# CHARGER.net
KiCad netlist of a schematic drawn in Altium Designer
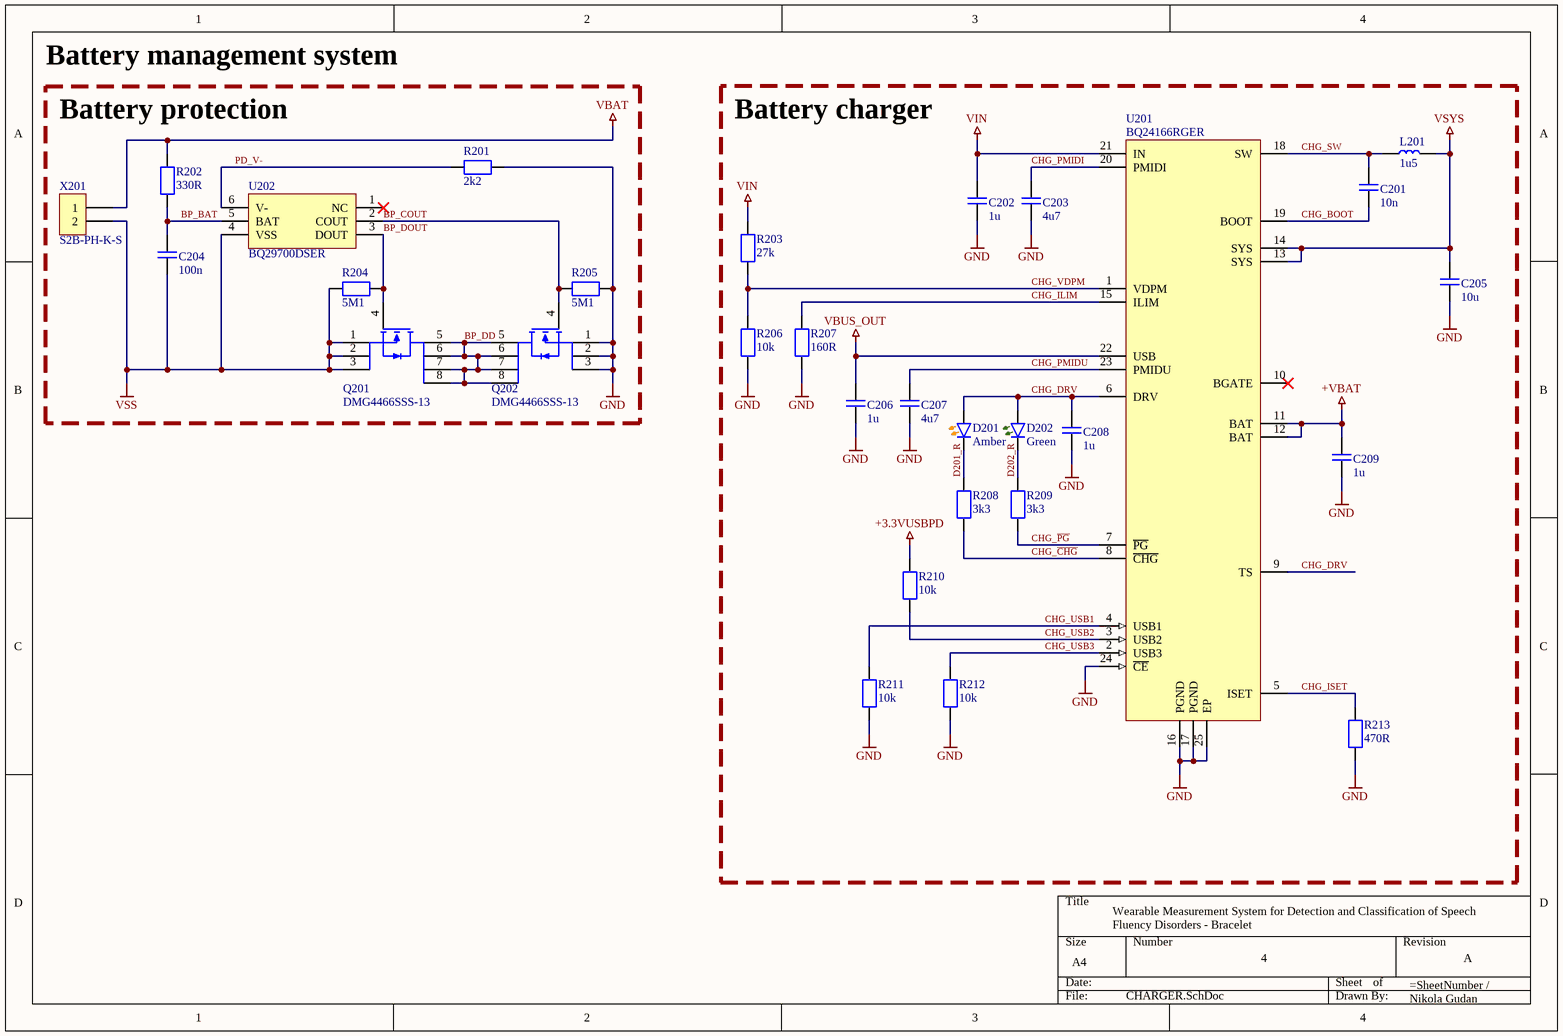
[diagram p0: CHARGER.SchDoc]

(export (version "E")
  (design (tool "Eeschema 10.0.6"))
  (components
    (comp (ref "C201")
      (value "10n")
      (footprint "CAPC0603")
      (description "Ceramic capacitor, 10nF,  50V, X7R")
      (fields (field (name "MFR") "KEMET") (field (name "CHECKED") "Yes"))
      (libsource (lib "NG_Passive") (part "CAPC0603-10n-20"))
    )
    (comp (ref "C202")
      (value "1u")
      (footprint "CAPC0603")
      (description "Ceramic capacitor, 1uF,  50V, X5R")
      (fields (field (name "MFR") "Murata Electronics") (field (name "CHECKED") "Yes"))
      (libsource (lib "NG_Passive") (part "CAPC0603-1u-10"))
    )
    (comp (ref "C203")
      (value "4u7")
      (footprint "CAPC0603")
      (description "Ceramic capacitor, 4.7uF, 25V, X5R")
      (fields (field (name "MFR") "TDK") (field (name "CHECKED") "Yes"))
      (libsource (lib "NG_Passive") (part "CAPC0603-4u7-10"))
    )
    (comp (ref "C204")
      (value "100n")
      (footprint "CAPC0603")
      (description "Ceramic capacitor, 100nF,  50V, X7R")
      (fields (field (name "MFR") "KEMET") (field (name "CHECKED") "Yes"))
      (libsource (lib "NG_Passive") (part "CAPC0603-100n-10"))
    )
    (comp (ref "C205")
      (value "10u")
      (footprint "CAPC0603")
      (description "Ceramic capacitor, 10uF,  25V, X5R")
      (fields (field (name "MFR") "TAIYO YUDEN") (field (name "CHECKED") "Yes"))
      (libsource (lib "NG_Passive") (part "CAPC0603-10u-20"))
    )
    (comp (ref "C206")
      (value "1u")
      (footprint "CAPC0603")
      (description "Ceramic capacitor, 1uF,  50V, X5R")
      (fields (field (name "MFR") "Murata Electronics") (field (name "CHECKED") "Yes"))
      (libsource (lib "NG_Passive") (part "CAPC0603-1u-10"))
    )
    (comp (ref "C207")
      (value "4u7")
      (footprint "CAPC0603")
      (description "Ceramic capacitor, 4.7uF, 25V, X5R")
      (fields (field (name "MFR") "TDK") (field (name "CHECKED") "Yes"))
      (libsource (lib "NG_Passive") (part "CAPC0603-4u7-10"))
    )
    (comp (ref "C208")
      (value "1u")
      (footprint "CAPC0603")
      (description "Ceramic capacitor, 1uF,  50V, X5R")
      (fields (field (name "MFR") "Murata Electronics") (field (name "CHECKED") "Yes"))
      (libsource (lib "NG_Passive") (part "CAPC0603-1u-10"))
    )
    (comp (ref "C209")
      (value "1u")
      (footprint "CAPC0603")
      (description "Ceramic capacitor, 1uF,  50V, X5R")
      (fields (field (name "MFR") "Murata Electronics") (field (name "CHECKED") "Yes"))
      (libsource (lib "NG_Passive") (part "CAPC0603-1u-10"))
    )
    (comp (ref "D201")
      (value "Amber")
      (footprint "LED0603")
      (description "LED Amber, 2V, 30mA")
      (fields (field (name "MFR") "Würth Elektronik") (field (name "CHECKED") "Yes"))
      (libsource (lib "NG_Active") (part "150060AS75000"))
    )
    (comp (ref "D202")
      (value "Green")
      (footprint "LED0603")
      (description "LED Green, 2.1V, 20mA")
      (fields (field (name "MFR") "Wurth Elektronik") (field (name "CHECKED") "Yes"))
      (libsource (lib "NG_Active") (part "150060GS75000"))
    )
    (comp (ref "L201")
      (value "1u5")
      (footprint "INDC1008")
      (description "Inductor 1.5uH, 3.3A, ±20%, 60mOhm")
      (fields (field (name "MFR") "TDK") (field (name "CHECKED") "Yes"))
      (libsource (lib "NG_Passive") (part "INDC1008-1u5-20"))
    )
    (comp (ref "Q201")
      (value "DMG4466SSS-13")
      (footprint "SOIC127P610X175-8")
      (description "MOSFET, N-CH, 30V, 10A")
      (fields (field (name "MFR") "Diodes Incorporated") (field (name "CHECKED") "Yes"))
      (libsource (lib "NG_Active") (part "DMG4466SSS-13"))
    )
    (comp (ref "Q202")
      (value "DMG4466SSS-13")
      (footprint "SOIC127P610X175-8")
      (description "MOSFET, N-CH, 30V, 10A")
      (fields (field (name "MFR") "Diodes Incorporated") (field (name "CHECKED") "Yes"))
      (libsource (lib "NG_Active") (part "DMG4466SSS-13"))
    )
    (comp (ref "R201")
      (value "2k2")
      (footprint "RESC0603")
      (description "Thick film resistor, 2.2kOhms, 100mW")
      (fields (field (name "MFR") "YAGEO") (field (name "CHECKED") "Yes"))
      (libsource (lib "NG_Passive") (part "RES0603-2k2-1"))
    )
    (comp (ref "R202")
      (value "330R")
      (footprint "RESC0603")
      (description "Thick film resistor, 330Ohms, 100mW")
      (fields (field (name "MFR") "YAGEO") (field (name "CHECKED") "Yes"))
      (libsource (lib "NG_Passive") (part "RES0603-330R-1"))
    )
    (comp (ref "R203")
      (value "27k")
      (footprint "RESC0603")
      (description "Thick film resistor, 27kOhm, 100mW")
      (fields (field (name "MFR") "YAGEO") (field (name "CHECKED") "Yes"))
      (libsource (lib "NG_Passive") (part "RES0603-27-1"))
    )
    (comp (ref "R204")
      (value "5M1")
      (footprint "RESC0603")
      (description "Thick film resistor, 5.1MOhms, 100mW")
      (fields (field (name "MFR") "YAGEO") (field (name "CHECKED") "Yes"))
      (libsource (lib "NG_Passive") (part "RES0603-5M1-1"))
    )
    (comp (ref "R205")
      (value "5M1")
      (footprint "RESC0603")
      (description "Thick film resistor, 5.1MOhms, 100mW")
      (fields (field (name "MFR") "YAGEO") (field (name "CHECKED") "Yes"))
      (libsource (lib "NG_Passive") (part "RES0603-5M1-1"))
    )
    (comp (ref "R206")
      (value "10k")
      (footprint "RESC0603")
      (description "Thick film resistor, 10kOhm, 100mW")
      (fields (field (name "MFR") "YAGEO") (field (name "CHECKED") "Yes"))
      (libsource (lib "NG_Passive") (part "RES0603-10k-1"))
    )
    (comp (ref "R207")
      (value "160R")
      (footprint "RESC0603")
      (description "Thick film resistor, 160Ohms, 100mW")
      (fields (field (name "MFR") "Panasonic") (field (name "CHECKED") "Yes"))
      (libsource (lib "NG_Passive") (part "RES0603-160R-1"))
    )
    (comp (ref "R208")
      (value "3k3")
      (footprint "RESC0603")
      (description "Thick film resistor, 3.3kOhms, 100mW")
      (fields (field (name "MFR") "YAGEO") (field (name "CHECKED") "Yes"))
      (libsource (lib "NG_Passive") (part "RES0603-3k3-1"))
    )
    (comp (ref "R209")
      (value "3k3")
      (footprint "RESC0603")
      (description "Thick film resistor, 3.3kOhms, 100mW")
      (fields (field (name "MFR") "YAGEO") (field (name "CHECKED") "Yes"))
      (libsource (lib "NG_Passive") (part "RES0603-3k3-1"))
    )
    (comp (ref "R210")
      (value "10k")
      (footprint "RESC0603")
      (description "Thick film resistor, 10kOhm, 100mW")
      (fields (field (name "MFR") "YAGEO") (field (name "CHECKED") "Yes"))
      (libsource (lib "NG_Passive") (part "RES0603-10k-1"))
    )
    (comp (ref "R211")
      (value "10k")
      (footprint "RESC0603")
      (description "Thick film resistor, 10kOhm, 100mW")
      (fields (field (name "MFR") "YAGEO") (field (name "CHECKED") "Yes"))
      (libsource (lib "NG_Passive") (part "RES0603-10k-1"))
    )
    (comp (ref "R212")
      (value "10k")
      (footprint "RESC0603")
      (description "Thick film resistor, 10kOhm, 100mW")
      (fields (field (name "MFR") "YAGEO") (field (name "CHECKED") "Yes"))
      (libsource (lib "NG_Passive") (part "RES0603-10k-1"))
    )
    (comp (ref "R213")
      (value "470R")
      (footprint "RESC0603")
      (description "Thick film resistor, 470R, 100mW")
      (fields (field (name "MFR") "YAGEO") (field (name "CHECKED") "Yes"))
      (libsource (lib "NG_Passive") (part "RES0603-470R-1"))
    )
    (comp (ref "U201")
      (value "BQ24166RGER")
      (footprint "QFN50P410X410X100-24EP")
      (description "IC Battery Charger, Li-Ion, 1 Cell, 3.7V, 2.5A")
      (fields (field (name "MFR") "Texas Instruments") (field (name "CHECKED") "Yes"))
      (libsource (lib "NG_Analog") (part "IC BATT CHG LI-ION BQ24166"))
    )
    (comp (ref "U202")
      (value "BQ29700DSER")
      (footprint "WSON50P150X150X80-6")
      (description "Battery Protection IC Li-Ion 1Cell")
      (fields (field (name "MFR") "Texas Instruments") (field (name "CHECKED") "Yes"))
      (libsource (lib "NG_Analog") (part "IC BATT PROT BQ29700DSER"))
    )
    (comp (ref "X201")
      (value "S2B-PH-K-S")
      (footprint "JST_S2B-PH-K-S")
      (description "JST PH Connector 2POS R/A THT")
      (fields (field (name "MFR") "JST Sales America Inc.") (field (name "CHECKED") "Yes"))
      (libsource (lib "NG_Mechanical") (part "JST S2B-PH-K-S"))
    )
  )
  (nets
    (net (code "1") (name "+3.3VUSBPD") (class "Default")
      (node (ref "R210") (pin "1") (pinfunction "1_1") (pintype "passive"))
    )
    (net (code "2") (name "+VBAT") (class "Default")
      (node (ref "C209") (pin "2") (pinfunction "2_2") (pintype "passive"))
      (node (ref "U201") (pin "11") (pinfunction "BAT_11") (pintype "power_in"))
      (node (ref "U201") (pin "12") (pinfunction "BAT_12") (pintype "power_in"))
    )
    (net (code "3") (name "/BP_BAT") (class "Default")
      (node (ref "C204") (pin "2") (pinfunction "2_2") (pintype "passive"))
      (node (ref "R202") (pin "1") (pinfunction "1_1") (pintype "passive"))
      (node (ref "U202") (pin "5") (pinfunction "BAT_5") (pintype "power_in"))
    )
    (net (code "4") (name "/BP_COUT") (class "Default")
      (node (ref "Q202") (pin "4") (pinfunction "G_4") (pintype "passive"))
      (node (ref "R205") (pin "2") (pinfunction "2_2") (pintype "passive"))
      (node (ref "U202") (pin "2") (pinfunction "COUT_2") (pintype "passive"))
    )
    (net (code "5") (name "/BP_DD") (class "Default")
      (node (ref "Q201") (pin "5") (pinfunction "D_5") (pintype "passive"))
      (node (ref "Q201") (pin "6") (pinfunction "D_6") (pintype "passive"))
      (node (ref "Q201") (pin "7") (pinfunction "D_7") (pintype "passive"))
      (node (ref "Q201") (pin "8") (pinfunction "D_8") (pintype "passive"))
      (node (ref "Q202") (pin "5") (pinfunction "D_5") (pintype "passive"))
      (node (ref "Q202") (pin "6") (pinfunction "D_6") (pintype "passive"))
      (node (ref "Q202") (pin "7") (pinfunction "D_7") (pintype "passive"))
      (node (ref "Q202") (pin "8") (pinfunction "D_8") (pintype "passive"))
    )
    (net (code "6") (name "/BP_DOUT") (class "Default")
      (node (ref "Q201") (pin "4") (pinfunction "G_4") (pintype "passive"))
      (node (ref "R204") (pin "1") (pinfunction "1_1") (pintype "passive"))
      (node (ref "U202") (pin "3") (pinfunction "DOUT_3") (pintype "passive"))
    )
    (net (code "7") (name "/CHG_BOOT") (class "Default")
      (node (ref "C201") (pin "1") (pinfunction "1_1") (pintype "passive"))
      (node (ref "U201") (pin "19") (pinfunction "BOOT_19") (pintype "passive"))
    )
    (net (code "8") (name "/CHG_DRV") (class "Default")
      (node (ref "C208") (pin "2") (pinfunction "2_2") (pintype "passive"))
      (node (ref "D201") (pin "2") (pinfunction "2_2") (pintype "passive"))
      (node (ref "D202") (pin "2") (pinfunction "2_2") (pintype "passive"))
      (node (ref "U201") (pin "6") (pinfunction "DRV_6") (pintype "passive"))
      (node (ref "U201") (pin "9") (pinfunction "TS_9") (pintype "passive"))
    )
    (net (code "9") (name "/CHG_ILIM") (class "Default")
      (node (ref "R207") (pin "1") (pinfunction "1_1") (pintype "passive"))
      (node (ref "U201") (pin "15") (pinfunction "ILIM_15") (pintype "power_in"))
    )
    (net (code "10") (name "/CHG_ISET") (class "Default")
      (node (ref "R213") (pin "2") (pinfunction "2_2") (pintype "passive"))
      (node (ref "U201") (pin "5") (pinfunction "ISET_5") (pintype "passive"))
    )
    (net (code "11") (name "/CHG_PMIDI") (class "Default")
      (node (ref "C203") (pin "2") (pinfunction "2_2") (pintype "passive"))
      (node (ref "U201") (pin "20") (pinfunction "PMIDI_20") (pintype "power_in"))
    )
    (net (code "12") (name "/CHG_PMIDU") (class "Default")
      (node (ref "C207") (pin "2") (pinfunction "2_2") (pintype "passive"))
      (node (ref "U201") (pin "23") (pinfunction "PMIDU_23") (pintype "power_in"))
    )
    (net (code "13") (name "/CHG_SW") (class "Default")
      (node (ref "C201") (pin "2") (pinfunction "2_2") (pintype "passive"))
      (node (ref "L201") (pin "1") (pinfunction "1_1") (pintype "passive"))
      (node (ref "U201") (pin "18") (pinfunction "SW_18") (pintype "power_in"))
    )
    (net (code "14") (name "/CHG_USB1") (class "Default")
      (node (ref "R211") (pin "1") (pinfunction "1_1") (pintype "passive"))
      (node (ref "U201") (pin "4") (pinfunction "USB1_4") (pintype "input"))
    )
    (net (code "15") (name "/CHG_USB2") (class "Default")
      (node (ref "R210") (pin "2") (pinfunction "2_2") (pintype "passive"))
      (node (ref "U201") (pin "3") (pinfunction "USB2_3") (pintype "input"))
    )
    (net (code "16") (name "/CHG_USB3") (class "Default")
      (node (ref "R212") (pin "1") (pinfunction "1_1") (pintype "passive"))
      (node (ref "U201") (pin "2") (pinfunction "USB3_2") (pintype "input"))
    )
    (net (code "17") (name "/CHG_VDPM") (class "Default")
      (node (ref "R203") (pin "1") (pinfunction "1_1") (pintype "passive"))
      (node (ref "R206") (pin "2") (pinfunction "2_2") (pintype "passive"))
      (node (ref "U201") (pin "1") (pinfunction "VDPM_1") (pintype "power_in"))
    )
    (net (code "18") (name "/CHG_~{CHG}") (class "Default")
      (node (ref "R208") (pin "1") (pinfunction "1_1") (pintype "passive"))
      (node (ref "U201") (pin "8") (pinfunction "~{CHG}_8") (pintype "open_collector"))
    )
    (net (code "19") (name "/CHG_~{PG}") (class "Default")
      (node (ref "R209") (pin "1") (pinfunction "1_1") (pintype "passive"))
      (node (ref "U201") (pin "7") (pinfunction "~{PG}_7") (pintype "open_collector"))
    )
    (net (code "20") (name "/D201_R") (class "Default")
      (node (ref "D201") (pin "1") (pinfunction "1_1") (pintype "passive"))
      (node (ref "R208") (pin "2") (pinfunction "2_2") (pintype "passive"))
    )
    (net (code "21") (name "/D202_R") (class "Default")
      (node (ref "D202") (pin "1") (pinfunction "1_1") (pintype "passive"))
      (node (ref "R209") (pin "2") (pinfunction "2_2") (pintype "passive"))
    )
    (net (code "22") (name "/PD_V-") (class "Default")
      (node (ref "R201") (pin "2") (pinfunction "2_2") (pintype "passive"))
      (node (ref "U202") (pin "6") (pinfunction "V-_6") (pintype "power_in"))
    )
    (net (code "23") (name "GND") (class "Default")
      (node (ref "C202") (pin "1") (pinfunction "1_1") (pintype "passive"))
      (node (ref "C203") (pin "1") (pinfunction "1_1") (pintype "passive"))
      (node (ref "C205") (pin "1") (pinfunction "1_1") (pintype "passive"))
      (node (ref "C206") (pin "1") (pinfunction "1_1") (pintype "passive"))
      (node (ref "C207") (pin "1") (pinfunction "1_1") (pintype "passive"))
      (node (ref "C208") (pin "1") (pinfunction "1_1") (pintype "passive"))
      (node (ref "C209") (pin "1") (pinfunction "1_1") (pintype "passive"))
      (node (ref "Q202") (pin "1") (pinfunction "S_1") (pintype "passive"))
      (node (ref "Q202") (pin "2") (pinfunction "S_2") (pintype "passive"))
      (node (ref "Q202") (pin "3") (pinfunction "S_3") (pintype "passive"))
      (node (ref "R201") (pin "1") (pinfunction "1_1") (pintype "passive"))
      (node (ref "R205") (pin "1") (pinfunction "1_1") (pintype "passive"))
      (node (ref "R206") (pin "1") (pinfunction "1_1") (pintype "passive"))
      (node (ref "R207") (pin "2") (pinfunction "2_2") (pintype "passive"))
      (node (ref "R211") (pin "2") (pinfunction "2_2") (pintype "passive"))
      (node (ref "R212") (pin "2") (pinfunction "2_2") (pintype "passive"))
      (node (ref "R213") (pin "1") (pinfunction "1_1") (pintype "passive"))
      (node (ref "U201") (pin "16") (pinfunction "PGND_16") (pintype "passive"))
      (node (ref "U201") (pin "17") (pinfunction "PGND_17") (pintype "passive"))
      (node (ref "U201") (pin "24") (pinfunction "~{CE}_24") (pintype "input"))
      (node (ref "U201") (pin "25") (pinfunction "EP_25") (pintype "passive"))
    )
    (net (code "24") (name "VBAT") (class "Default")
      (node (ref "R202") (pin "2") (pinfunction "2_2") (pintype "passive"))
      (node (ref "X201") (pin "1") (pinfunction "1_1") (pintype "passive"))
    )
    (net (code "25") (name "VBUS_OUT") (class "Default")
      (node (ref "C206") (pin "2") (pinfunction "2_2") (pintype "passive"))
      (node (ref "U201") (pin "22") (pinfunction "USB_22") (pintype "power_in"))
    )
    (net (code "26") (name "VIN") (class "Default")
      (node (ref "C202") (pin "2") (pinfunction "2_2") (pintype "passive"))
      (node (ref "R203") (pin "2") (pinfunction "2_2") (pintype "passive"))
      (node (ref "U201") (pin "21") (pinfunction "IN_21") (pintype "power_in"))
    )
    (net (code "27") (name "VSS") (class "Default")
      (node (ref "C204") (pin "1") (pinfunction "1_1") (pintype "passive"))
      (node (ref "Q201") (pin "1") (pinfunction "S_1") (pintype "passive"))
      (node (ref "Q201") (pin "2") (pinfunction "S_2") (pintype "passive"))
      (node (ref "Q201") (pin "3") (pinfunction "S_3") (pintype "passive"))
      (node (ref "R204") (pin "2") (pinfunction "2_2") (pintype "passive"))
      (node (ref "U202") (pin "4") (pinfunction "VSS_4") (pintype "power_in"))
      (node (ref "X201") (pin "2") (pinfunction "2_2") (pintype "passive"))
    )
    (net (code "28") (name "VSYS") (class "Default")
      (node (ref "C205") (pin "2") (pinfunction "2_2") (pintype "passive"))
      (node (ref "L201") (pin "2") (pinfunction "2_2") (pintype "passive"))
      (node (ref "U201") (pin "13") (pinfunction "SYS_13") (pintype "passive"))
      (node (ref "U201") (pin "14") (pinfunction "SYS_14") (pintype "passive"))
    )
    (net (code "29") (name "unconnected-(U201-BGATE-Pad10)") (class "Default")
      (node (ref "U201") (pin "10") (pinfunction "BGATE_10") (pintype "tri_state+no_connect"))
    )
    (net (code "30") (name "unconnected-(U202-NC-Pad1)") (class "Default")
      (node (ref "U202") (pin "1") (pinfunction "NC_1") (pintype "passive+no_connect"))
    )
  )
)
